# MTCH_bob.net
KiCad netlist of a schematic drawn in EAGLE
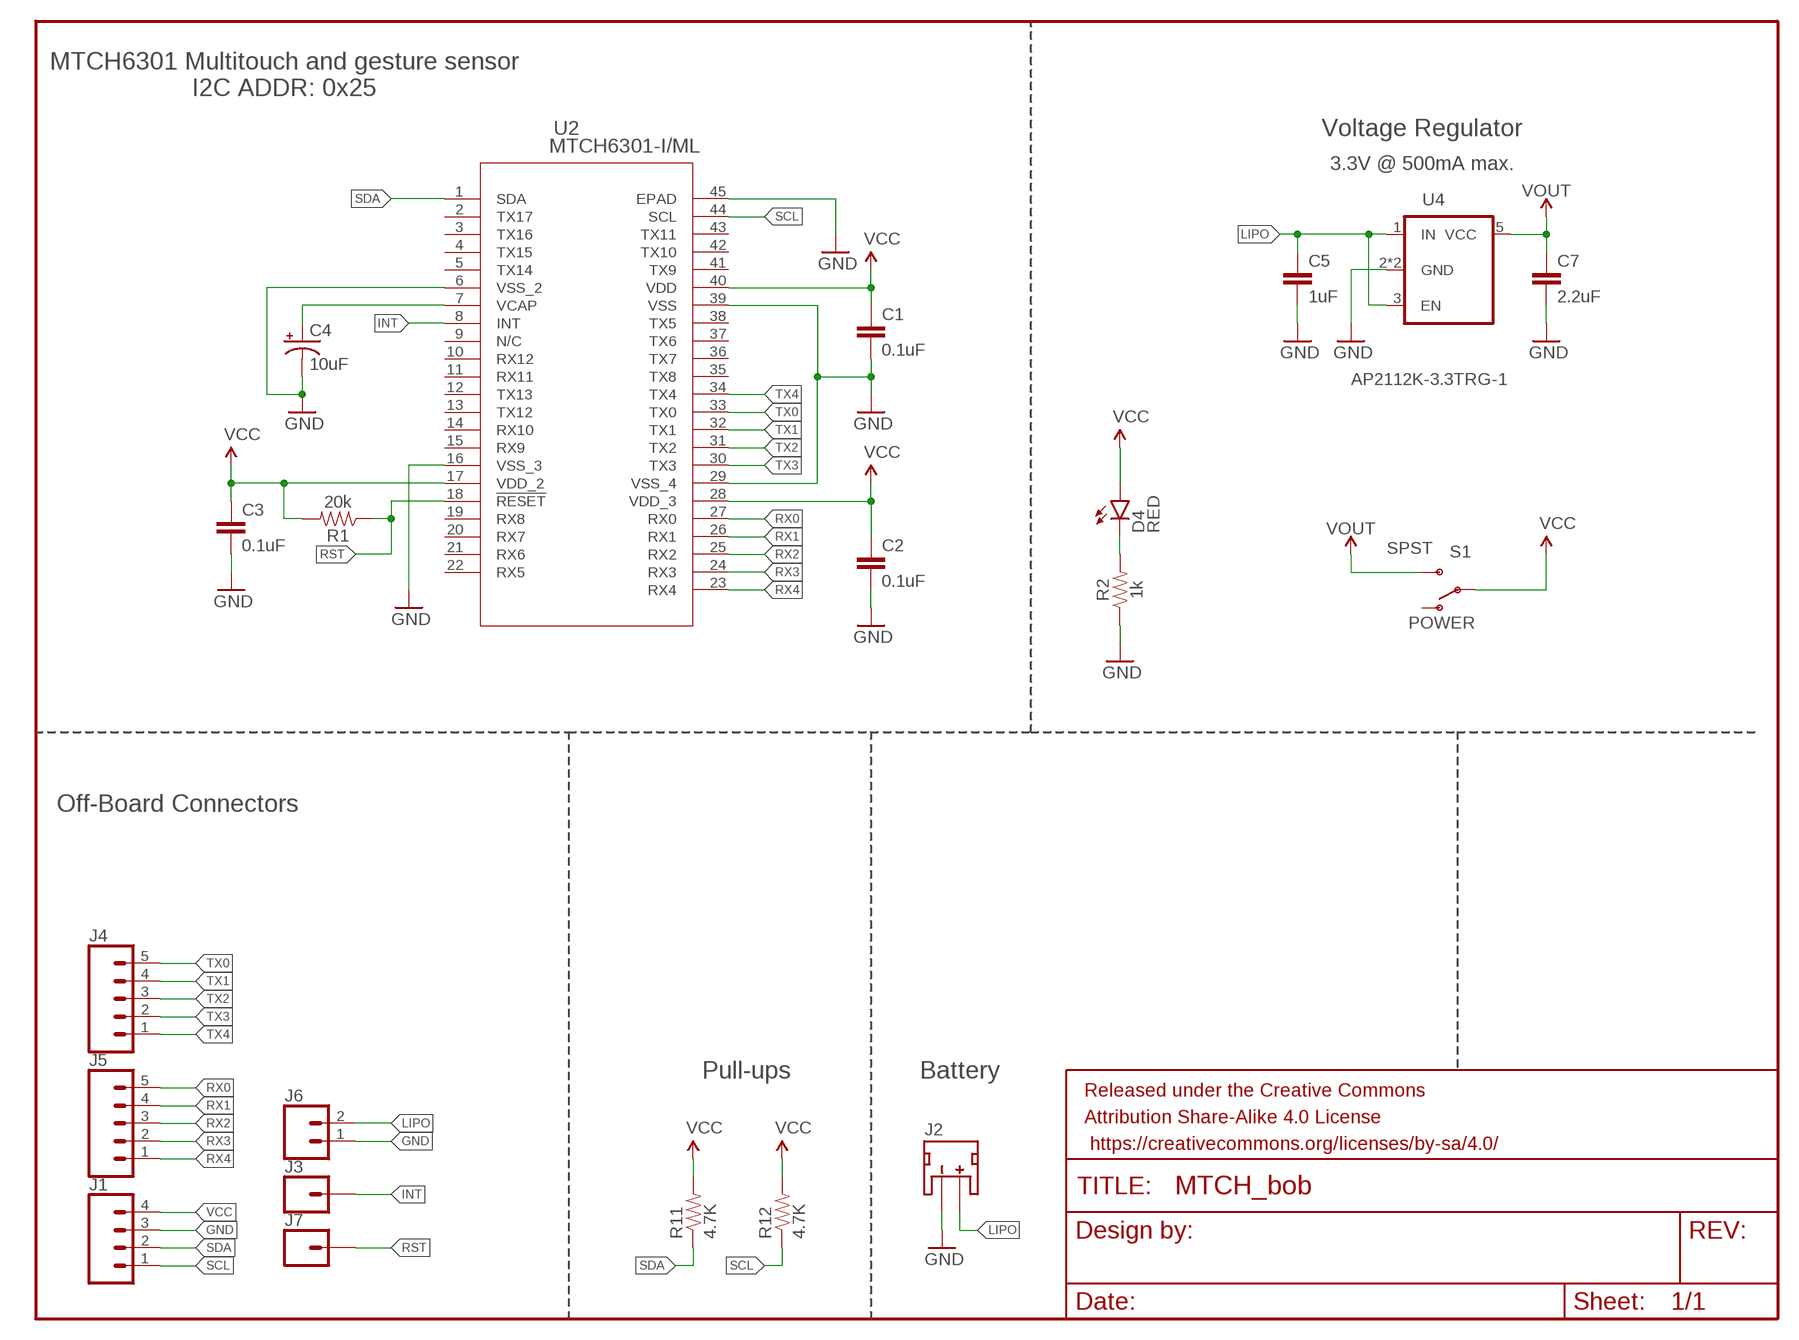
[diagram p0: schematic, sheet 1]

(export (version "E")
  (design (tool "Eeschema 10.0.6"))
  (components
    (comp (ref "C1")
      (value "0.1uF")
      (footprint "eagle-import:0603")
      (libsource (lib "eagle-import") (part "0.1UF-0603-25V-(+80/-20%)"))
    )
    (comp (ref "C2")
      (value "0.1uF")
      (footprint "eagle-import:0603")
      (libsource (lib "eagle-import") (part "0.1UF-0603-25V-(+80/-20%)"))
    )
    (comp (ref "C3")
      (value "0.1uF")
      (footprint "eagle-import:0603")
      (libsource (lib "eagle-import") (part "0.1UF-0603-25V-(+80/-20%)"))
    )
    (comp (ref "C4")
      (value "10uF")
      (footprint "eagle-import:EIA3528")
      (libsource (lib "eagle-import") (part "10UF-POLAR-EIA3528-20V-10%(TANT)"))
    )
    (comp (ref "C5")
      (value "1uF")
      (footprint "eagle-import:0603-CAP")
      (libsource (lib "eagle-import") (part "CAP0603-CAP"))
    )
    (comp (ref "C7")
      (value "2.2uF")
      (footprint "eagle-import:0603-CAP")
      (libsource (lib "eagle-import") (part "2.2UF-10V-20%(0603)"))
    )
    (comp (ref "D4")
      (value "RED")
      (footprint "eagle-import:LED-1206")
      (libsource (lib "eagle-import") (part "LED-RED1206"))
    )
    (comp (ref "FRAME1")
      (value "FRAME-LETTERNO_PACKAGE")
      (footprint "eagle-import:DUMMY")
      (fields (field (name "DESIGNER") "Nobody"))
      (libsource (lib "eagle-import") (part "FRAME-LETTERNO_PACKAGE"))
    )
    (comp (ref "J1")
      (value "CONN_04")
      (footprint "eagle-import:1X04")
      (libsource (lib "eagle-import") (part "CONN_04"))
    )
    (comp (ref "J2")
      (value "LiPo")
      (footprint "eagle-import:JST-2-SMD")
      (libsource (lib "eagle-import") (part "JST_2MM_MALE"))
    )
    (comp (ref "J3")
      (value "CONN_01")
      (footprint "eagle-import:1X01")
      (libsource (lib "eagle-import") (part "CONN_01"))
    )
    (comp (ref "J4")
      (value "CONN_05")
      (footprint "eagle-import:1X05")
      (libsource (lib "eagle-import") (part "CONN_05"))
    )
    (comp (ref "J5")
      (value "CONN_05")
      (footprint "eagle-import:1X05")
      (libsource (lib "eagle-import") (part "CONN_05"))
    )
    (comp (ref "J6")
      (value "CONN_02")
      (footprint "eagle-import:1X02")
      (libsource (lib "eagle-import") (part "CONN_02"))
    )
    (comp (ref "J7")
      (value "CONN_01")
      (footprint "eagle-import:1X01")
      (libsource (lib "eagle-import") (part "CONN_01"))
    )
    (comp (ref "R1")
      (value "20k")
      (footprint "eagle-import:0603")
      (libsource (lib "eagle-import") (part "20KOHM-0603-1/10W-1%"))
    )
    (comp (ref "R2")
      (value "1k")
      (footprint "eagle-import:0603")
      (libsource (lib "eagle-import") (part "1KOHM-0603-1/10W-1%"))
    )
    (comp (ref "R11")
      (value "4.7K")
      (footprint "eagle-import:0603-RES")
      (libsource (lib "eagle-import") (part "RESISTOR0603-RES"))
    )
    (comp (ref "R12")
      (value "4.7K")
      (footprint "eagle-import:0603-RES")
      (libsource (lib "eagle-import") (part "RESISTOR0603-RES"))
    )
    (comp (ref "S1")
      (value "POWER")
      (footprint "eagle-import:SWITCH-SPST-SMD-A")
      (libsource (lib "eagle-import") (part "SWITCH-SPDT-SMD-A"))
    )
    (comp (ref "U2")
      (value "MTCH6301-I/ML")
      (footprint "eagle-import:QFN44_8X8MC_MCH")
      (fields (field (name "COPYRIGHT") "Copyright (C) 2021 Ultra Librarian. All rights reserved."))
      (libsource (lib "eagle-import") (part "MTCH6301-I/ML"))
    )
    (comp (ref "U4")
      (value "AP2112K-3.3TRG-1")
      (footprint "eagle-import:SOT23-5")
      (libsource (lib "eagle-import") (part "LDO-TPS78233"))
    )
  )
  (nets
    (net (code "1") (name "GND") (class "Default")
      (node (ref "C1") (pin "2") (pinfunction "2_2") (pintype "passive"))
      (node (ref "C2") (pin "2") (pinfunction "2_2") (pintype "passive"))
      (node (ref "C3") (pin "2") (pinfunction "2_2") (pintype "passive"))
      (node (ref "C4") (pin "C") (pinfunction "-_C") (pintype "passive"))
      (node (ref "C5") (pin "2") (pinfunction "2_2") (pintype "passive"))
      (node (ref "C7") (pin "2") (pinfunction "2_2") (pintype "passive"))
      (node (ref "J1") (pin "3") (pinfunction "3_3") (pintype "passive"))
      (node (ref "J2") (pin "1") (pinfunction "-_1") (pintype "bidirectional"))
      (node (ref "J6") (pin "1") (pinfunction "1_1") (pintype "passive"))
      (node (ref "R2") (pin "1") (pinfunction "1_1") (pintype "passive"))
      (node (ref "U2") (pin "16") (pinfunction "VSS_3_16") (pintype "passive"))
      (node (ref "U2") (pin "29") (pinfunction "VSS_4_29") (pintype "passive"))
      (node (ref "U2") (pin "39") (pinfunction "VSS_39") (pintype "passive"))
      (node (ref "U2") (pin "45") (pinfunction "EPAD_45") (pintype "passive"))
      (node (ref "U2") (pin "6") (pinfunction "VSS_2_6") (pintype "power_in"))
      (node (ref "U4") (pin "2") (pinfunction "GND_2") (pintype "input"))
      (node (ref "U4") (pin "4") (pinfunction "GND_4") (pintype "input"))
    )
    (net (code "2") (name "INT") (class "Default")
      (node (ref "J3") (pin "1") (pinfunction "1_1") (pintype "passive"))
      (node (ref "U2") (pin "8") (pinfunction "INT_8") (pintype "output"))
    )
    (net (code "3") (name "LIPO") (class "Default")
      (node (ref "C5") (pin "1") (pinfunction "1_1") (pintype "passive"))
      (node (ref "J2") (pin "2") (pinfunction "+_2") (pintype "bidirectional"))
      (node (ref "J6") (pin "2") (pinfunction "2_2") (pintype "passive"))
      (node (ref "U4") (pin "1") (pinfunction "IN_1") (pintype "input"))
      (node (ref "U4") (pin "3") (pinfunction "EN_3") (pintype "input"))
    )
    (net (code "4") (name "Net-(C4-+)") (class "Default")
      (node (ref "C4") (pin "A") (pinfunction "+_A") (pintype "passive"))
      (node (ref "U2") (pin "7") (pinfunction "VCAP_7") (pintype "power_in"))
    )
    (net (code "5") (name "Net-(D4-PadC)") (class "Default")
      (node (ref "D4") (pin "C") (pinfunction "C_C") (pintype "passive"))
      (node (ref "R2") (pin "2") (pinfunction "2_2") (pintype "passive"))
    )
    (net (code "6") (name "RST") (class "Default")
      (node (ref "J7") (pin "1") (pinfunction "1_1") (pintype "passive"))
      (node (ref "R1") (pin "1") (pinfunction "1_1") (pintype "passive"))
      (node (ref "U2") (pin "18") (pinfunction "~{RESET}_18") (pintype "input"))
    )
    (net (code "7") (name "RX0") (class "Default")
      (node (ref "J5") (pin "5") (pinfunction "5_5") (pintype "passive"))
      (node (ref "U2") (pin "27") (pinfunction "RX0_27") (pintype "bidirectional"))
    )
    (net (code "8") (name "RX1") (class "Default")
      (node (ref "J5") (pin "4") (pinfunction "4_4") (pintype "passive"))
      (node (ref "U2") (pin "26") (pinfunction "RX1_26") (pintype "bidirectional"))
    )
    (net (code "9") (name "RX2") (class "Default")
      (node (ref "J5") (pin "3") (pinfunction "3_3") (pintype "passive"))
      (node (ref "U2") (pin "25") (pinfunction "RX2_25") (pintype "bidirectional"))
    )
    (net (code "10") (name "RX3") (class "Default")
      (node (ref "J5") (pin "2") (pinfunction "2_2") (pintype "passive"))
      (node (ref "U2") (pin "24") (pinfunction "RX3_24") (pintype "bidirectional"))
    )
    (net (code "11") (name "RX4") (class "Default")
      (node (ref "J5") (pin "1") (pinfunction "1_1") (pintype "passive"))
      (node (ref "U2") (pin "23") (pinfunction "RX4_23") (pintype "bidirectional"))
    )
    (net (code "12") (name "SCL") (class "Default")
      (node (ref "J1") (pin "1") (pinfunction "1_1") (pintype "passive"))
      (node (ref "R12") (pin "1") (pinfunction "1_1") (pintype "passive"))
      (node (ref "U2") (pin "44") (pinfunction "SCL_44") (pintype "input"))
    )
    (net (code "13") (name "SDA") (class "Default")
      (node (ref "J1") (pin "2") (pinfunction "2_2") (pintype "passive"))
      (node (ref "R11") (pin "1") (pinfunction "1_1") (pintype "passive"))
      (node (ref "U2") (pin "1") (pinfunction "SDA_1") (pintype "bidirectional"))
    )
    (net (code "14") (name "TX0") (class "Default")
      (node (ref "J4") (pin "5") (pinfunction "5_5") (pintype "passive"))
      (node (ref "U2") (pin "33") (pinfunction "TX0_33") (pintype "bidirectional"))
    )
    (net (code "15") (name "TX1") (class "Default")
      (node (ref "J4") (pin "4") (pinfunction "4_4") (pintype "passive"))
      (node (ref "U2") (pin "32") (pinfunction "TX1_32") (pintype "bidirectional"))
    )
    (net (code "16") (name "TX2") (class "Default")
      (node (ref "J4") (pin "3") (pinfunction "3_3") (pintype "passive"))
      (node (ref "U2") (pin "31") (pinfunction "TX2_31") (pintype "bidirectional"))
    )
    (net (code "17") (name "TX3") (class "Default")
      (node (ref "J4") (pin "2") (pinfunction "2_2") (pintype "passive"))
      (node (ref "U2") (pin "30") (pinfunction "TX3_30") (pintype "bidirectional"))
    )
    (net (code "18") (name "TX4") (class "Default")
      (node (ref "J4") (pin "1") (pinfunction "1_1") (pintype "passive"))
      (node (ref "U2") (pin "34") (pinfunction "TX4_34") (pintype "bidirectional"))
    )
    (net (code "19") (name "VCC") (class "Default")
      (node (ref "C1") (pin "1") (pinfunction "1_1") (pintype "passive"))
      (node (ref "C2") (pin "1") (pinfunction "1_1") (pintype "passive"))
      (node (ref "C3") (pin "1") (pinfunction "1_1") (pintype "passive"))
      (node (ref "D4") (pin "A") (pinfunction "A_A") (pintype "passive"))
      (node (ref "J1") (pin "4") (pinfunction "4_4") (pintype "passive"))
      (node (ref "R1") (pin "2") (pinfunction "2_2") (pintype "passive"))
      (node (ref "R11") (pin "2") (pinfunction "2_2") (pintype "passive"))
      (node (ref "R12") (pin "2") (pinfunction "2_2") (pintype "passive"))
      (node (ref "S1") (pin "2") (pinfunction "P_2") (pintype "passive"))
      (node (ref "U2") (pin "17") (pinfunction "VDD_2_17") (pintype "power_in"))
      (node (ref "U2") (pin "28") (pinfunction "VDD_3_28") (pintype "power_in"))
      (node (ref "U2") (pin "40") (pinfunction "VDD_40") (pintype "power_in"))
    )
    (net (code "20") (name "VOUT") (class "Default")
      (node (ref "C7") (pin "1") (pinfunction "1_1") (pintype "passive"))
      (node (ref "S1") (pin "3") (pinfunction "S_3") (pintype "passive"))
      (node (ref "U4") (pin "5") (pinfunction "VCC_5") (pintype "power_in"))
    )
    (net (code "21") (name "unconnected-(J2-PAD1-PadNC1)") (class "Default")
      (node (ref "J2") (pin "NC1") (pinfunction "PAD1_NC1") (pintype "bidirectional"))
    )
    (net (code "22") (name "unconnected-(J2-PAD2-PadNC2)") (class "Default")
      (node (ref "J2") (pin "NC2") (pinfunction "PAD2_NC2") (pintype "bidirectional"))
    )
    (net (code "23") (name "unconnected-(S1-O-Pad1)") (class "Default")
      (node (ref "S1") (pin "1") (pinfunction "O_1") (pintype "passive"))
    )
    (net (code "24") (name "unconnected-(U2-N{slash}C-Pad9)") (class "Default")
      (node (ref "U2") (pin "9") (pinfunction "N/C_9") (pintype "no_connect"))
    )
    (net (code "25") (name "unconnected-(U2-RX5-Pad22)") (class "Default")
      (node (ref "U2") (pin "22") (pinfunction "RX5_22") (pintype "bidirectional"))
    )
    (net (code "26") (name "unconnected-(U2-RX6-Pad21)") (class "Default")
      (node (ref "U2") (pin "21") (pinfunction "RX6_21") (pintype "bidirectional"))
    )
    (net (code "27") (name "unconnected-(U2-RX7-Pad20)") (class "Default")
      (node (ref "U2") (pin "20") (pinfunction "RX7_20") (pintype "bidirectional"))
    )
    (net (code "28") (name "unconnected-(U2-RX8-Pad19)") (class "Default")
      (node (ref "U2") (pin "19") (pinfunction "RX8_19") (pintype "bidirectional"))
    )
    (net (code "29") (name "unconnected-(U2-RX9-Pad15)") (class "Default")
      (node (ref "U2") (pin "15") (pinfunction "RX9_15") (pintype "bidirectional"))
    )
    (net (code "30") (name "unconnected-(U2-RX10-Pad14)") (class "Default")
      (node (ref "U2") (pin "14") (pinfunction "RX10_14") (pintype "bidirectional"))
    )
    (net (code "31") (name "unconnected-(U2-RX11-Pad11)") (class "Default")
      (node (ref "U2") (pin "11") (pinfunction "RX11_11") (pintype "bidirectional"))
    )
    (net (code "32") (name "unconnected-(U2-RX12-Pad10)") (class "Default")
      (node (ref "U2") (pin "10") (pinfunction "RX12_10") (pintype "bidirectional"))
    )
    (net (code "33") (name "unconnected-(U2-TX5-Pad38)") (class "Default")
      (node (ref "U2") (pin "38") (pinfunction "TX5_38") (pintype "bidirectional"))
    )
    (net (code "34") (name "unconnected-(U2-TX6-Pad37)") (class "Default")
      (node (ref "U2") (pin "37") (pinfunction "TX6_37") (pintype "bidirectional"))
    )
    (net (code "35") (name "unconnected-(U2-TX7-Pad36)") (class "Default")
      (node (ref "U2") (pin "36") (pinfunction "TX7_36") (pintype "bidirectional"))
    )
    (net (code "36") (name "unconnected-(U2-TX8-Pad35)") (class "Default")
      (node (ref "U2") (pin "35") (pinfunction "TX8_35") (pintype "bidirectional"))
    )
    (net (code "37") (name "unconnected-(U2-TX9-Pad41)") (class "Default")
      (node (ref "U2") (pin "41") (pinfunction "TX9_41") (pintype "bidirectional"))
    )
    (net (code "38") (name "unconnected-(U2-TX10-Pad42)") (class "Default")
      (node (ref "U2") (pin "42") (pinfunction "TX10_42") (pintype "bidirectional"))
    )
    (net (code "39") (name "unconnected-(U2-TX11-Pad43)") (class "Default")
      (node (ref "U2") (pin "43") (pinfunction "TX11_43") (pintype "bidirectional"))
    )
    (net (code "40") (name "unconnected-(U2-TX12-Pad13)") (class "Default")
      (node (ref "U2") (pin "13") (pinfunction "TX12_13") (pintype "bidirectional"))
    )
    (net (code "41") (name "unconnected-(U2-TX13-Pad12)") (class "Default")
      (node (ref "U2") (pin "12") (pinfunction "TX13_12") (pintype "bidirectional"))
    )
    (net (code "42") (name "unconnected-(U2-TX14-Pad5)") (class "Default")
      (node (ref "U2") (pin "5") (pinfunction "TX14_5") (pintype "bidirectional"))
    )
    (net (code "43") (name "unconnected-(U2-TX15-Pad4)") (class "Default")
      (node (ref "U2") (pin "4") (pinfunction "TX15_4") (pintype "bidirectional"))
    )
    (net (code "44") (name "unconnected-(U2-TX16-Pad3)") (class "Default")
      (node (ref "U2") (pin "3") (pinfunction "TX16_3") (pintype "bidirectional"))
    )
    (net (code "45") (name "unconnected-(U2-TX17-Pad2)") (class "Default")
      (node (ref "U2") (pin "2") (pinfunction "TX17_2") (pintype "bidirectional"))
    )
  )
)
